# MdkController.net
KiCad netlist of a schematic drawn in EAGLE
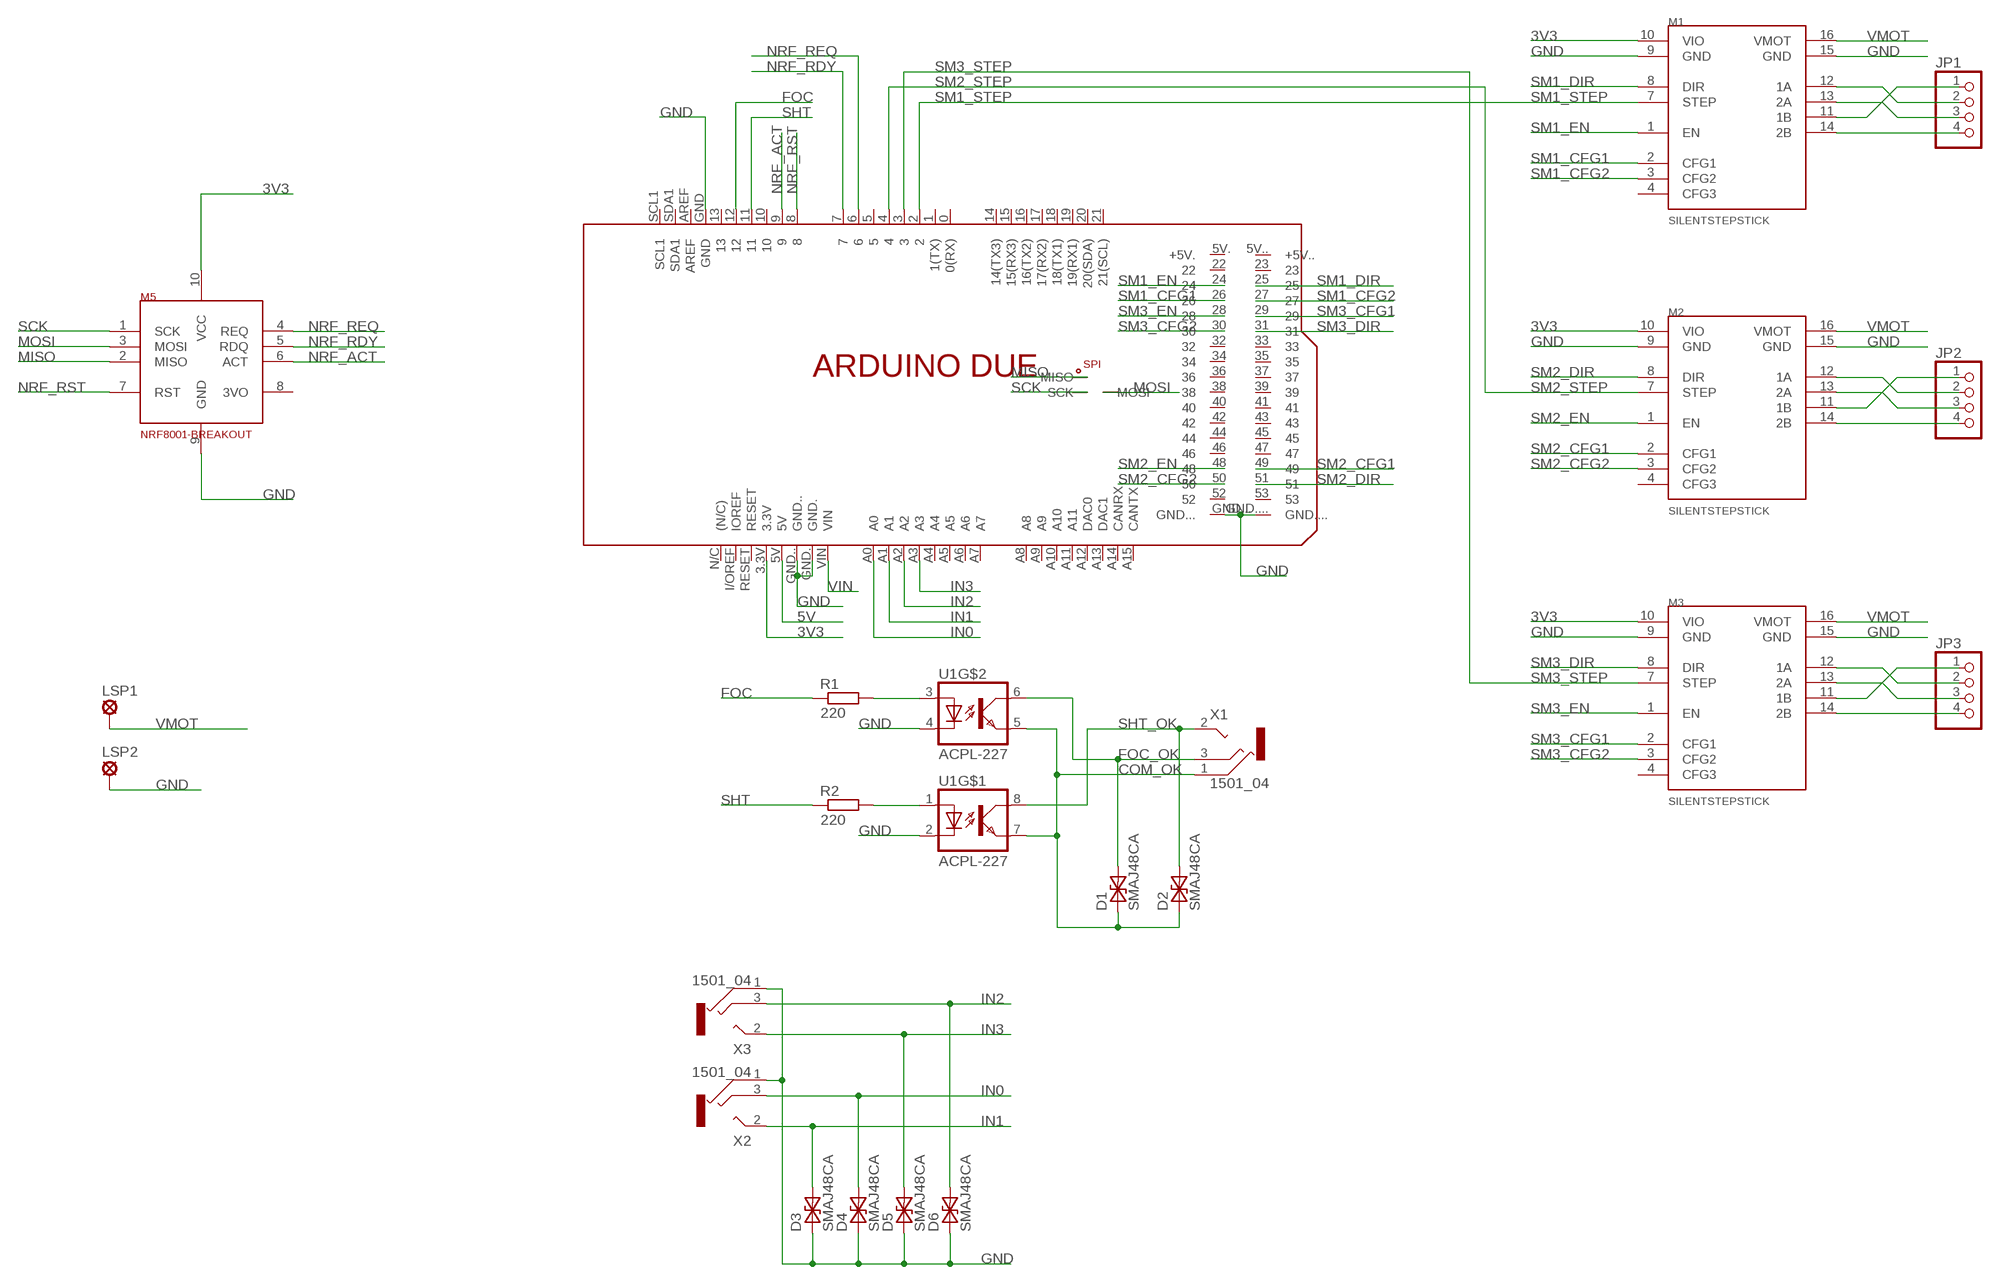
[diagram p0: schematic, sheet 1]

(export (version "E")
  (design (tool "Eeschema 10.0.6"))
  (components
    (comp (ref "D1")
      (value "SMAJ48CA")
      (footprint "eagle-import:DO214AC")
      (libsource (lib "eagle-import") (part "SMAJCA48"))
    )
    (comp (ref "D2")
      (value "SMAJ48CA")
      (footprint "eagle-import:DO214AC")
      (libsource (lib "eagle-import") (part "SMAJCA48"))
    )
    (comp (ref "D3")
      (value "SMAJ48CA")
      (footprint "eagle-import:DO214AC")
      (libsource (lib "eagle-import") (part "SMAJCA48"))
    )
    (comp (ref "D4")
      (value "SMAJ48CA")
      (footprint "eagle-import:DO214AC")
      (libsource (lib "eagle-import") (part "SMAJCA48"))
    )
    (comp (ref "D5")
      (value "SMAJ48CA")
      (footprint "eagle-import:DO214AC")
      (libsource (lib "eagle-import") (part "SMAJCA48"))
    )
    (comp (ref "D6")
      (value "SMAJ48CA")
      (footprint "eagle-import:DO214AC")
      (libsource (lib "eagle-import") (part "SMAJCA48"))
    )
    (comp (ref "JP1")
      (value "PINHD-1X4")
      (footprint "eagle-import:1X04")
      (libsource (lib "eagle-import") (part "PINHD-1X4"))
    )
    (comp (ref "JP2")
      (value "PINHD-1X4")
      (footprint "eagle-import:1X04")
      (libsource (lib "eagle-import") (part "PINHD-1X4"))
    )
    (comp (ref "JP3")
      (value "PINHD-1X4")
      (footprint "eagle-import:1X04")
      (libsource (lib "eagle-import") (part "PINHD-1X4"))
    )
    (comp (ref "LSP1")
      (value "SE14")
      (footprint "eagle-import:SE14")
      (libsource (lib "eagle-import") (part "SE14"))
    )
    (comp (ref "LSP2")
      (value "SE14")
      (footprint "eagle-import:SE14")
      (libsource (lib "eagle-import") (part "SE14"))
    )
    (comp (ref "M1")
      (value "SILENTSTEPSTICK")
      (footprint "eagle-import:SILENTSTEPSTICK")
      (libsource (lib "eagle-import") (part "SILENTSTEPSTICK"))
    )
    (comp (ref "M2")
      (value "SILENTSTEPSTICK")
      (footprint "eagle-import:SILENTSTEPSTICK")
      (libsource (lib "eagle-import") (part "SILENTSTEPSTICK"))
    )
    (comp (ref "M3")
      (value "SILENTSTEPSTICK")
      (footprint "eagle-import:SILENTSTEPSTICK")
      (libsource (lib "eagle-import") (part "SILENTSTEPSTICK"))
    )
    (comp (ref "M5")
      (value "NRF8001-BREAKOUT")
      (footprint "eagle-import:NRF8001-BREAKOUT")
      (libsource (lib "eagle-import") (part "NRF8001-BREAKOUT"))
    )
    (comp (ref "R1")
      (value "220")
      (footprint "eagle-import:R0805")
      (libsource (lib "eagle-import") (part "R-EU_R0805"))
    )
    (comp (ref "R2")
      (value "220")
      (footprint "eagle-import:R0805")
      (libsource (lib "eagle-import") (part "R-EU_R0805"))
    )
    (comp (ref "U$1")
      (value "ARDUINO_DUE_PINS_ONLY")
      (footprint "eagle-import:ARDUINO_DUE_PINS_ONLY")
      (libsource (lib "eagle-import") (part "ARDUINO_DUE_PINS_ONLY"))
    )
    (comp (ref "U1")
      (value "ACPL-227")
      (footprint "eagle-import:SO8")
      (libsource (lib "eagle-import") (part "ACPL-227"))
    )
    (comp (ref "X1")
      (value "1501_04")
      (footprint "eagle-import:1501_05")
      (libsource (lib "eagle-import") (part "1501_04"))
    )
    (comp (ref "X2")
      (value "1501_04")
      (footprint "eagle-import:1501_05")
      (libsource (lib "eagle-import") (part "1501_04"))
    )
    (comp (ref "X3")
      (value "1501_04")
      (footprint "eagle-import:1501_05")
      (libsource (lib "eagle-import") (part "1501_04"))
    )
  )
  (nets
    (net (code "1") (name "/3V3") (class "Default")
      (node (ref "M1") (pin "10") (pinfunction "VIO_10") (pintype "power_in"))
      (node (ref "M2") (pin "10") (pinfunction "VIO_10") (pintype "power_in"))
      (node (ref "M3") (pin "10") (pinfunction "VIO_10") (pintype "power_in"))
      (node (ref "M5") (pin "10") (pinfunction "VCC_10") (pintype "power_in"))
      (node (ref "U$1") (pin "3.3V") (pinfunction "3.3V_3.3V") (pintype "bidirectional"))
    )
    (net (code "2") (name "/5V") (class "Default")
      (node (ref "U$1") (pin "5V") (pinfunction "5V_5V") (pintype "bidirectional"))
    )
    (net (code "3") (name "/COM_OK") (class "Default")
      (node (ref "D1") (pin "1") (pinfunction "1_1") (pintype "passive"))
      (node (ref "D2") (pin "1") (pinfunction "1_1") (pintype "passive"))
      (node (ref "U1") (pin "5") (pinfunction "EMIT_5") (pintype "passive"))
      (node (ref "U1") (pin "7") (pinfunction "EMIT_7") (pintype "passive"))
      (node (ref "X1") (pin "1") (pinfunction "1_1") (pintype "passive"))
    )
    (net (code "4") (name "/FOC") (class "Default")
      (node (ref "R1") (pin "1") (pinfunction "1_1") (pintype "passive"))
      (node (ref "U$1") (pin "12") (pinfunction "12_12") (pintype "bidirectional"))
    )
    (net (code "5") (name "/FOC_OK") (class "Default")
      (node (ref "D1") (pin "2") (pinfunction "2_2") (pintype "passive"))
      (node (ref "U1") (pin "6") (pinfunction "COL_6") (pintype "passive"))
      (node (ref "X1") (pin "3") (pinfunction "3_3") (pintype "passive"))
    )
    (net (code "6") (name "/GND") (class "Default")
      (node (ref "D3") (pin "1") (pinfunction "1_1") (pintype "passive"))
      (node (ref "D4") (pin "1") (pinfunction "1_1") (pintype "passive"))
      (node (ref "D5") (pin "1") (pinfunction "1_1") (pintype "passive"))
      (node (ref "D6") (pin "1") (pinfunction "1_1") (pintype "passive"))
      (node (ref "LSP2") (pin "MP") (pinfunction "MP_MP") (pintype "passive"))
      (node (ref "M1") (pin "15") (pinfunction "GND_15") (pintype "power_in"))
      (node (ref "M1") (pin "9") (pinfunction "GND_9") (pintype "power_in"))
      (node (ref "M2") (pin "15") (pinfunction "GND_15") (pintype "power_in"))
      (node (ref "M2") (pin "9") (pinfunction "GND_9") (pintype "power_in"))
      (node (ref "M3") (pin "15") (pinfunction "GND_15") (pintype "power_in"))
      (node (ref "M3") (pin "9") (pinfunction "GND_9") (pintype "power_in"))
      (node (ref "M5") (pin "9") (pinfunction "GND_9") (pintype "power_in"))
      (node (ref "U$1") (pin "GND") (pinfunction "GND_GND") (pintype "bidirectional"))
      (node (ref "U$1") (pin "GND.") (pinfunction "GND._GND.") (pintype "bidirectional"))
      (node (ref "U$1") (pin "GND..") (pinfunction "GND.._GND..") (pintype "bidirectional"))
      (node (ref "U$1") (pin "GND...") (pinfunction "GND..._GND...") (pintype "bidirectional"))
      (node (ref "U$1") (pin "GND....") (pinfunction "GND...._GND....") (pintype "bidirectional"))
      (node (ref "U1") (pin "2") (pinfunction "C_2") (pintype "passive"))
      (node (ref "U1") (pin "4") (pinfunction "C_4") (pintype "passive"))
      (node (ref "X2") (pin "1") (pinfunction "1_1") (pintype "passive"))
      (node (ref "X3") (pin "1") (pinfunction "1_1") (pintype "passive"))
    )
    (net (code "7") (name "/IN0") (class "Default")
      (node (ref "D4") (pin "2") (pinfunction "2_2") (pintype "passive"))
      (node (ref "U$1") (pin "A0") (pinfunction "A0_A0") (pintype "bidirectional"))
      (node (ref "X2") (pin "3") (pinfunction "3_3") (pintype "passive"))
    )
    (net (code "8") (name "/IN1") (class "Default")
      (node (ref "D3") (pin "2") (pinfunction "2_2") (pintype "passive"))
      (node (ref "U$1") (pin "A1") (pinfunction "A1_A1") (pintype "bidirectional"))
      (node (ref "X2") (pin "2") (pinfunction "2_2") (pintype "passive"))
    )
    (net (code "9") (name "/IN2") (class "Default")
      (node (ref "D6") (pin "2") (pinfunction "2_2") (pintype "passive"))
      (node (ref "U$1") (pin "A2") (pinfunction "A2_A2") (pintype "bidirectional"))
      (node (ref "X3") (pin "3") (pinfunction "3_3") (pintype "passive"))
    )
    (net (code "10") (name "/IN3") (class "Default")
      (node (ref "D5") (pin "2") (pinfunction "2_2") (pintype "passive"))
      (node (ref "U$1") (pin "A3") (pinfunction "A3_A3") (pintype "bidirectional"))
      (node (ref "X3") (pin "2") (pinfunction "2_2") (pintype "passive"))
    )
    (net (code "11") (name "/MISO") (class "Default")
      (node (ref "M5") (pin "2") (pinfunction "MISO_2") (pintype "output"))
      (node (ref "U$1") (pin "MISO") (pinfunction "MISO_MISO") (pintype "bidirectional"))
    )
    (net (code "12") (name "/MOSI") (class "Default")
      (node (ref "M5") (pin "3") (pinfunction "MOSI_3") (pintype "input"))
      (node (ref "U$1") (pin "MOSI") (pinfunction "MOSI_MOSI") (pintype "bidirectional"))
    )
    (net (code "13") (name "/NRF_ACT") (class "Default")
      (node (ref "M5") (pin "6") (pinfunction "ACT_6") (pintype "output"))
      (node (ref "U$1") (pin "9") (pinfunction "9_9") (pintype "bidirectional"))
    )
    (net (code "14") (name "/NRF_RDY") (class "Default")
      (node (ref "M5") (pin "5") (pinfunction "RDQ_5") (pintype "output"))
      (node (ref "U$1") (pin "7") (pinfunction "7_7") (pintype "bidirectional"))
    )
    (net (code "15") (name "/NRF_REQ") (class "Default")
      (node (ref "M5") (pin "4") (pinfunction "REQ_4") (pintype "input"))
      (node (ref "U$1") (pin "6") (pinfunction "6_6") (pintype "bidirectional"))
    )
    (net (code "16") (name "/NRF_RST") (class "Default")
      (node (ref "M5") (pin "7") (pinfunction "RST_7") (pintype "input"))
      (node (ref "U$1") (pin "8") (pinfunction "8_8") (pintype "bidirectional"))
    )
    (net (code "17") (name "/SCK") (class "Default")
      (node (ref "M5") (pin "1") (pinfunction "SCK_1") (pintype "input"))
      (node (ref "U$1") (pin "SCK") (pinfunction "SCK_SCK") (pintype "bidirectional"))
    )
    (net (code "18") (name "/SHT") (class "Default")
      (node (ref "R2") (pin "1") (pinfunction "1_1") (pintype "passive"))
      (node (ref "U$1") (pin "11") (pinfunction "11_11") (pintype "bidirectional"))
    )
    (net (code "19") (name "/SHT_OK") (class "Default")
      (node (ref "D2") (pin "2") (pinfunction "2_2") (pintype "passive"))
      (node (ref "U1") (pin "8") (pinfunction "COL_8") (pintype "passive"))
      (node (ref "X1") (pin "2") (pinfunction "2_2") (pintype "passive"))
    )
    (net (code "20") (name "/SM1_CFG1") (class "Default")
      (node (ref "M1") (pin "2") (pinfunction "CFG1_2") (pintype "input"))
      (node (ref "U$1") (pin "26") (pinfunction "26_26") (pintype "bidirectional"))
    )
    (net (code "21") (name "/SM1_CFG2") (class "Default")
      (node (ref "M1") (pin "3") (pinfunction "CFG2_3") (pintype "input"))
      (node (ref "U$1") (pin "27") (pinfunction "27_27") (pintype "bidirectional"))
    )
    (net (code "22") (name "/SM1_DIR") (class "Default")
      (node (ref "M1") (pin "8") (pinfunction "DIR_8") (pintype "input"))
      (node (ref "U$1") (pin "25") (pinfunction "25_25") (pintype "bidirectional"))
    )
    (net (code "23") (name "/SM1_EN") (class "Default")
      (node (ref "M1") (pin "1") (pinfunction "EN_1") (pintype "input"))
      (node (ref "U$1") (pin "24") (pinfunction "24_24") (pintype "bidirectional"))
    )
    (net (code "24") (name "/SM1_STEP") (class "Default")
      (node (ref "M1") (pin "7") (pinfunction "STEP_7") (pintype "input"))
      (node (ref "U$1") (pin "2") (pinfunction "2_2") (pintype "bidirectional"))
    )
    (net (code "25") (name "/SM2_CFG1") (class "Default")
      (node (ref "M2") (pin "2") (pinfunction "CFG1_2") (pintype "input"))
      (node (ref "U$1") (pin "49") (pinfunction "49_49") (pintype "bidirectional"))
    )
    (net (code "26") (name "/SM2_CFG2") (class "Default")
      (node (ref "M2") (pin "3") (pinfunction "CFG2_3") (pintype "input"))
      (node (ref "U$1") (pin "50") (pinfunction "50_50") (pintype "bidirectional"))
    )
    (net (code "27") (name "/SM2_DIR") (class "Default")
      (node (ref "M2") (pin "8") (pinfunction "DIR_8") (pintype "input"))
      (node (ref "U$1") (pin "51") (pinfunction "51_51") (pintype "bidirectional"))
    )
    (net (code "28") (name "/SM2_EN") (class "Default")
      (node (ref "M2") (pin "1") (pinfunction "EN_1") (pintype "input"))
      (node (ref "U$1") (pin "48") (pinfunction "48_48") (pintype "bidirectional"))
    )
    (net (code "29") (name "/SM2_STEP") (class "Default")
      (node (ref "M2") (pin "7") (pinfunction "STEP_7") (pintype "input"))
      (node (ref "U$1") (pin "4") (pinfunction "4_4") (pintype "bidirectional"))
    )
    (net (code "30") (name "/SM3_CFG1") (class "Default")
      (node (ref "M3") (pin "2") (pinfunction "CFG1_2") (pintype "input"))
      (node (ref "U$1") (pin "29") (pinfunction "29_29") (pintype "bidirectional"))
    )
    (net (code "31") (name "/SM3_CFG2") (class "Default")
      (node (ref "M3") (pin "3") (pinfunction "CFG2_3") (pintype "input"))
      (node (ref "U$1") (pin "30") (pinfunction "30_30") (pintype "bidirectional"))
    )
    (net (code "32") (name "/SM3_DIR") (class "Default")
      (node (ref "M3") (pin "8") (pinfunction "DIR_8") (pintype "input"))
      (node (ref "U$1") (pin "31") (pinfunction "31_31") (pintype "bidirectional"))
    )
    (net (code "33") (name "/SM3_EN") (class "Default")
      (node (ref "M3") (pin "1") (pinfunction "EN_1") (pintype "input"))
      (node (ref "U$1") (pin "28") (pinfunction "28_28") (pintype "bidirectional"))
    )
    (net (code "34") (name "/SM3_STEP") (class "Default")
      (node (ref "M3") (pin "7") (pinfunction "STEP_7") (pintype "input"))
      (node (ref "U$1") (pin "3") (pinfunction "3_3") (pintype "bidirectional"))
    )
    (net (code "35") (name "/VIN") (class "Default")
      (node (ref "U$1") (pin "VIN") (pinfunction "VIN_VIN") (pintype "bidirectional"))
    )
    (net (code "36") (name "/VMOT") (class "Default")
      (node (ref "LSP1") (pin "MP") (pinfunction "MP_MP") (pintype "passive"))
      (node (ref "M1") (pin "16") (pinfunction "VMOT_16") (pintype "power_in"))
      (node (ref "M2") (pin "16") (pinfunction "VMOT_16") (pintype "power_in"))
      (node (ref "M3") (pin "16") (pinfunction "VMOT_16") (pintype "power_in"))
    )
    (net (code "37") (name "Net-(M1-1A)") (class "Default")
      (node (ref "JP1") (pin "2") (pinfunction "2_2") (pintype "passive"))
      (node (ref "M1") (pin "12") (pinfunction "1A_12") (pintype "output"))
    )
    (net (code "38") (name "Net-(M1-1B)") (class "Default")
      (node (ref "JP1") (pin "1") (pinfunction "1_1") (pintype "passive"))
      (node (ref "M1") (pin "11") (pinfunction "1B_11") (pintype "output"))
    )
    (net (code "39") (name "Net-(M1-2A)") (class "Default")
      (node (ref "JP1") (pin "3") (pinfunction "3_3") (pintype "passive"))
      (node (ref "M1") (pin "13") (pinfunction "2A_13") (pintype "output"))
    )
    (net (code "40") (name "Net-(M1-2B)") (class "Default")
      (node (ref "JP1") (pin "4") (pinfunction "4_4") (pintype "passive"))
      (node (ref "M1") (pin "14") (pinfunction "2B_14") (pintype "output"))
    )
    (net (code "41") (name "Net-(M2-1A)") (class "Default")
      (node (ref "JP2") (pin "2") (pinfunction "2_2") (pintype "passive"))
      (node (ref "M2") (pin "12") (pinfunction "1A_12") (pintype "output"))
    )
    (net (code "42") (name "Net-(M2-1B)") (class "Default")
      (node (ref "JP2") (pin "1") (pinfunction "1_1") (pintype "passive"))
      (node (ref "M2") (pin "11") (pinfunction "1B_11") (pintype "output"))
    )
    (net (code "43") (name "Net-(M2-2A)") (class "Default")
      (node (ref "JP2") (pin "3") (pinfunction "3_3") (pintype "passive"))
      (node (ref "M2") (pin "13") (pinfunction "2A_13") (pintype "output"))
    )
    (net (code "44") (name "Net-(M2-2B)") (class "Default")
      (node (ref "JP2") (pin "4") (pinfunction "4_4") (pintype "passive"))
      (node (ref "M2") (pin "14") (pinfunction "2B_14") (pintype "output"))
    )
    (net (code "45") (name "Net-(M3-1A)") (class "Default")
      (node (ref "JP3") (pin "2") (pinfunction "2_2") (pintype "passive"))
      (node (ref "M3") (pin "12") (pinfunction "1A_12") (pintype "output"))
    )
    (net (code "46") (name "Net-(M3-1B)") (class "Default")
      (node (ref "JP3") (pin "1") (pinfunction "1_1") (pintype "passive"))
      (node (ref "M3") (pin "11") (pinfunction "1B_11") (pintype "output"))
    )
    (net (code "47") (name "Net-(M3-2A)") (class "Default")
      (node (ref "JP3") (pin "3") (pinfunction "3_3") (pintype "passive"))
      (node (ref "M3") (pin "13") (pinfunction "2A_13") (pintype "output"))
    )
    (net (code "48") (name "Net-(M3-2B)") (class "Default")
      (node (ref "JP3") (pin "4") (pinfunction "4_4") (pintype "passive"))
      (node (ref "M3") (pin "14") (pinfunction "2B_14") (pintype "output"))
    )
    (net (code "49") (name "Net-(U1A-A)") (class "Default")
      (node (ref "R2") (pin "2") (pinfunction "2_2") (pintype "passive"))
      (node (ref "U1") (pin "1") (pinfunction "A_1") (pintype "passive"))
    )
    (net (code "50") (name "Net-(U1B-A)") (class "Default")
      (node (ref "R1") (pin "2") (pinfunction "2_2") (pintype "passive"))
      (node (ref "U1") (pin "3") (pinfunction "A_3") (pintype "passive"))
    )
    (net (code "51") (name "unconnected-(M1-CFG3-Pad4)") (class "Default")
      (node (ref "M1") (pin "4") (pinfunction "CFG3_4") (pintype "input"))
    )
    (net (code "52") (name "unconnected-(M2-CFG3-Pad4)") (class "Default")
      (node (ref "M2") (pin "4") (pinfunction "CFG3_4") (pintype "input"))
    )
    (net (code "53") (name "unconnected-(M3-CFG3-Pad4)") (class "Default")
      (node (ref "M3") (pin "4") (pinfunction "CFG3_4") (pintype "input"))
    )
    (net (code "54") (name "unconnected-(M5-3VO-Pad8)") (class "Default")
      (node (ref "M5") (pin "8") (pinfunction "3VO_8") (pintype "output"))
    )
    (net (code "55") (name "unconnected-(U$1-(N{slash}C)-PadN{slash}C)") (class "Default")
      (node (ref "U$1") (pin "N/C") (pinfunction "(N/C)_N/C") (pintype "bidirectional"))
    )
    (net (code "56") (name "unconnected-(U$1-+5V.-Pad5V.)") (class "Default")
      (node (ref "U$1") (pin "5V.") (pinfunction "+5V._5V.") (pintype "bidirectional"))
    )
    (net (code "57") (name "unconnected-(U$1-+5V..-Pad5V..)") (class "Default")
      (node (ref "U$1") (pin "5V..") (pinfunction "+5V.._5V..") (pintype "bidirectional"))
    )
    (net (code "58") (name "unconnected-(U$1-0(RX)-Pad0)") (class "Default")
      (node (ref "U$1") (pin "0") (pinfunction "0(RX)_0") (pintype "bidirectional"))
    )
    (net (code "59") (name "unconnected-(U$1-1(TX)-Pad1)") (class "Default")
      (node (ref "U$1") (pin "1") (pinfunction "1(TX)_1") (pintype "bidirectional"))
    )
    (net (code "60") (name "unconnected-(U$1-14(TX3)-Pad14)") (class "Default")
      (node (ref "U$1") (pin "14") (pinfunction "14(TX3)_14") (pintype "bidirectional"))
    )
    (net (code "61") (name "unconnected-(U$1-15(RX3)-Pad15)") (class "Default")
      (node (ref "U$1") (pin "15") (pinfunction "15(RX3)_15") (pintype "bidirectional"))
    )
    (net (code "62") (name "unconnected-(U$1-16(TX2)-Pad16)") (class "Default")
      (node (ref "U$1") (pin "16") (pinfunction "16(TX2)_16") (pintype "bidirectional"))
    )
    (net (code "63") (name "unconnected-(U$1-17(RX2)-Pad17)") (class "Default")
      (node (ref "U$1") (pin "17") (pinfunction "17(RX2)_17") (pintype "bidirectional"))
    )
    (net (code "64") (name "unconnected-(U$1-18(TX1)-Pad18)") (class "Default")
      (node (ref "U$1") (pin "18") (pinfunction "18(TX1)_18") (pintype "bidirectional"))
    )
    (net (code "65") (name "unconnected-(U$1-19(RX1)-Pad19)") (class "Default")
      (node (ref "U$1") (pin "19") (pinfunction "19(RX1)_19") (pintype "bidirectional"))
    )
    (net (code "66") (name "unconnected-(U$1-20(SDA)-Pad20)") (class "Default")
      (node (ref "U$1") (pin "20") (pinfunction "20(SDA)_20") (pintype "bidirectional"))
    )
    (net (code "67") (name "unconnected-(U$1-21(SCL)-Pad21)") (class "Default")
      (node (ref "U$1") (pin "21") (pinfunction "21(SCL)_21") (pintype "bidirectional"))
    )
    (net (code "68") (name "unconnected-(U$1-CANRX-PadA14)") (class "Default")
      (node (ref "U$1") (pin "A14") (pinfunction "CANRX_A14") (pintype "bidirectional"))
    )
    (net (code "69") (name "unconnected-(U$1-CANTX-PadA15)") (class "Default")
      (node (ref "U$1") (pin "A15") (pinfunction "CANTX_A15") (pintype "bidirectional"))
    )
    (net (code "70") (name "unconnected-(U$1-DAC0-PadA12)") (class "Default")
      (node (ref "U$1") (pin "A12") (pinfunction "DAC0_A12") (pintype "bidirectional"))
    )
    (net (code "71") (name "unconnected-(U$1-DAC1-PadA13)") (class "Default")
      (node (ref "U$1") (pin "A13") (pinfunction "DAC1_A13") (pintype "bidirectional"))
    )
    (net (code "72") (name "unconnected-(U$1-IOREF-PadI{slash}OREF)") (class "Default")
      (node (ref "U$1") (pin "I/OREF") (pinfunction "IOREF_I/OREF") (pintype "bidirectional"))
    )
    (net (code "73") (name "unconnected-(U$1-Pad+5V_)") (class "Default")
      (node (ref "U$1") (pin "+5V_") (pinfunction "+5V__+5V_") (pintype "bidirectional"))
    )
    (net (code "74") (name "unconnected-(U$1-Pad5)") (class "Default")
      (node (ref "U$1") (pin "5") (pinfunction "5_5") (pintype "bidirectional"))
    )
    (net (code "75") (name "unconnected-(U$1-Pad10)") (class "Default")
      (node (ref "U$1") (pin "10") (pinfunction "10_10") (pintype "bidirectional"))
    )
    (net (code "76") (name "unconnected-(U$1-Pad13)") (class "Default")
      (node (ref "U$1") (pin "13") (pinfunction "13_13") (pintype "bidirectional"))
    )
    (net (code "77") (name "unconnected-(U$1-Pad22)") (class "Default")
      (node (ref "U$1") (pin "22") (pinfunction "22_22") (pintype "bidirectional"))
    )
    (net (code "78") (name "unconnected-(U$1-Pad23)") (class "Default")
      (node (ref "U$1") (pin "23") (pinfunction "23_23") (pintype "bidirectional"))
    )
    (net (code "79") (name "unconnected-(U$1-Pad32)") (class "Default")
      (node (ref "U$1") (pin "32") (pinfunction "32_32") (pintype "bidirectional"))
    )
    (net (code "80") (name "unconnected-(U$1-Pad33)") (class "Default")
      (node (ref "U$1") (pin "33") (pinfunction "33_33") (pintype "bidirectional"))
    )
    (net (code "81") (name "unconnected-(U$1-Pad34)") (class "Default")
      (node (ref "U$1") (pin "34") (pinfunction "34_34") (pintype "bidirectional"))
    )
    (net (code "82") (name "unconnected-(U$1-Pad35)") (class "Default")
      (node (ref "U$1") (pin "35") (pinfunction "35_35") (pintype "bidirectional"))
    )
    (net (code "83") (name "unconnected-(U$1-Pad36)") (class "Default")
      (node (ref "U$1") (pin "36") (pinfunction "36_36") (pintype "bidirectional"))
    )
    (net (code "84") (name "unconnected-(U$1-Pad37)") (class "Default")
      (node (ref "U$1") (pin "37") (pinfunction "37_37") (pintype "bidirectional"))
    )
    (net (code "85") (name "unconnected-(U$1-Pad38)") (class "Default")
      (node (ref "U$1") (pin "38") (pinfunction "38_38") (pintype "bidirectional"))
    )
    (net (code "86") (name "unconnected-(U$1-Pad39)") (class "Default")
      (node (ref "U$1") (pin "39") (pinfunction "39_39") (pintype "bidirectional"))
    )
    (net (code "87") (name "unconnected-(U$1-Pad40)") (class "Default")
      (node (ref "U$1") (pin "40") (pinfunction "40_40") (pintype "bidirectional"))
    )
    (net (code "88") (name "unconnected-(U$1-Pad41)") (class "Default")
      (node (ref "U$1") (pin "41") (pinfunction "41_41") (pintype "bidirectional"))
    )
    (net (code "89") (name "unconnected-(U$1-Pad42)") (class "Default")
      (node (ref "U$1") (pin "42") (pinfunction "42_42") (pintype "bidirectional"))
    )
    (net (code "90") (name "unconnected-(U$1-Pad43)") (class "Default")
      (node (ref "U$1") (pin "43") (pinfunction "43_43") (pintype "bidirectional"))
    )
    (net (code "91") (name "unconnected-(U$1-Pad44)") (class "Default")
      (node (ref "U$1") (pin "44") (pinfunction "44_44") (pintype "bidirectional"))
    )
    (net (code "92") (name "unconnected-(U$1-Pad45)") (class "Default")
      (node (ref "U$1") (pin "45") (pinfunction "45_45") (pintype "bidirectional"))
    )
    (net (code "93") (name "unconnected-(U$1-Pad46)") (class "Default")
      (node (ref "U$1") (pin "46") (pinfunction "46_46") (pintype "bidirectional"))
    )
    (net (code "94") (name "unconnected-(U$1-Pad47)") (class "Default")
      (node (ref "U$1") (pin "47") (pinfunction "47_47") (pintype "bidirectional"))
    )
    (net (code "95") (name "unconnected-(U$1-Pad52)") (class "Default")
      (node (ref "U$1") (pin "52") (pinfunction "52_52") (pintype "bidirectional"))
    )
    (net (code "96") (name "unconnected-(U$1-Pad53)") (class "Default")
      (node (ref "U$1") (pin "53") (pinfunction "53_53") (pintype "bidirectional"))
    )
    (net (code "97") (name "unconnected-(U$1-PadA4)") (class "Default")
      (node (ref "U$1") (pin "A4") (pinfunction "A4_A4") (pintype "bidirectional"))
    )
    (net (code "98") (name "unconnected-(U$1-PadA5)") (class "Default")
      (node (ref "U$1") (pin "A5") (pinfunction "A5_A5") (pintype "bidirectional"))
    )
    (net (code "99") (name "unconnected-(U$1-PadA6)") (class "Default")
      (node (ref "U$1") (pin "A6") (pinfunction "A6_A6") (pintype "bidirectional"))
    )
    (net (code "100") (name "unconnected-(U$1-PadA7)") (class "Default")
      (node (ref "U$1") (pin "A7") (pinfunction "A7_A7") (pintype "bidirectional"))
    )
    (net (code "101") (name "unconnected-(U$1-PadA8)") (class "Default")
      (node (ref "U$1") (pin "A8") (pinfunction "A8_A8") (pintype "bidirectional"))
    )
    (net (code "102") (name "unconnected-(U$1-PadA9)") (class "Default")
      (node (ref "U$1") (pin "A9") (pinfunction "A9_A9") (pintype "bidirectional"))
    )
    (net (code "103") (name "unconnected-(U$1-PadA10)") (class "Default")
      (node (ref "U$1") (pin "A10") (pinfunction "A10_A10") (pintype "bidirectional"))
    )
    (net (code "104") (name "unconnected-(U$1-PadA11)") (class "Default")
      (node (ref "U$1") (pin "A11") (pinfunction "A11_A11") (pintype "bidirectional"))
    )
    (net (code "105") (name "unconnected-(U$1-PadAREF)") (class "Default")
      (node (ref "U$1") (pin "AREF") (pinfunction "AREF_AREF") (pintype "bidirectional"))
    )
    (net (code "106") (name "unconnected-(U$1-PadGND__)") (class "Default")
      (node (ref "U$1") (pin "GND__") (pinfunction "GND___GND__") (pintype "bidirectional"))
    )
    (net (code "107") (name "unconnected-(U$1-PadRESET)") (class "Default")
      (node (ref "U$1") (pin "RESET") (pinfunction "RESET_RESET") (pintype "bidirectional"))
    )
    (net (code "108") (name "unconnected-(U$1-PadRESET.)") (class "Default")
      (node (ref "U$1") (pin "RESET.") (pinfunction "RESET._RESET.") (pintype "bidirectional"))
    )
    (net (code "109") (name "unconnected-(U$1-PadSCL1)") (class "Default")
      (node (ref "U$1") (pin "SCL1") (pinfunction "SCL1_SCL1") (pintype "bidirectional"))
    )
    (net (code "110") (name "unconnected-(U$1-PadSDA1)") (class "Default")
      (node (ref "U$1") (pin "SDA1") (pinfunction "SDA1_SDA1") (pintype "bidirectional"))
    )
  )
)
